# Motor_2.net
KiCad netlist of a schematic drawn in Altium Designer
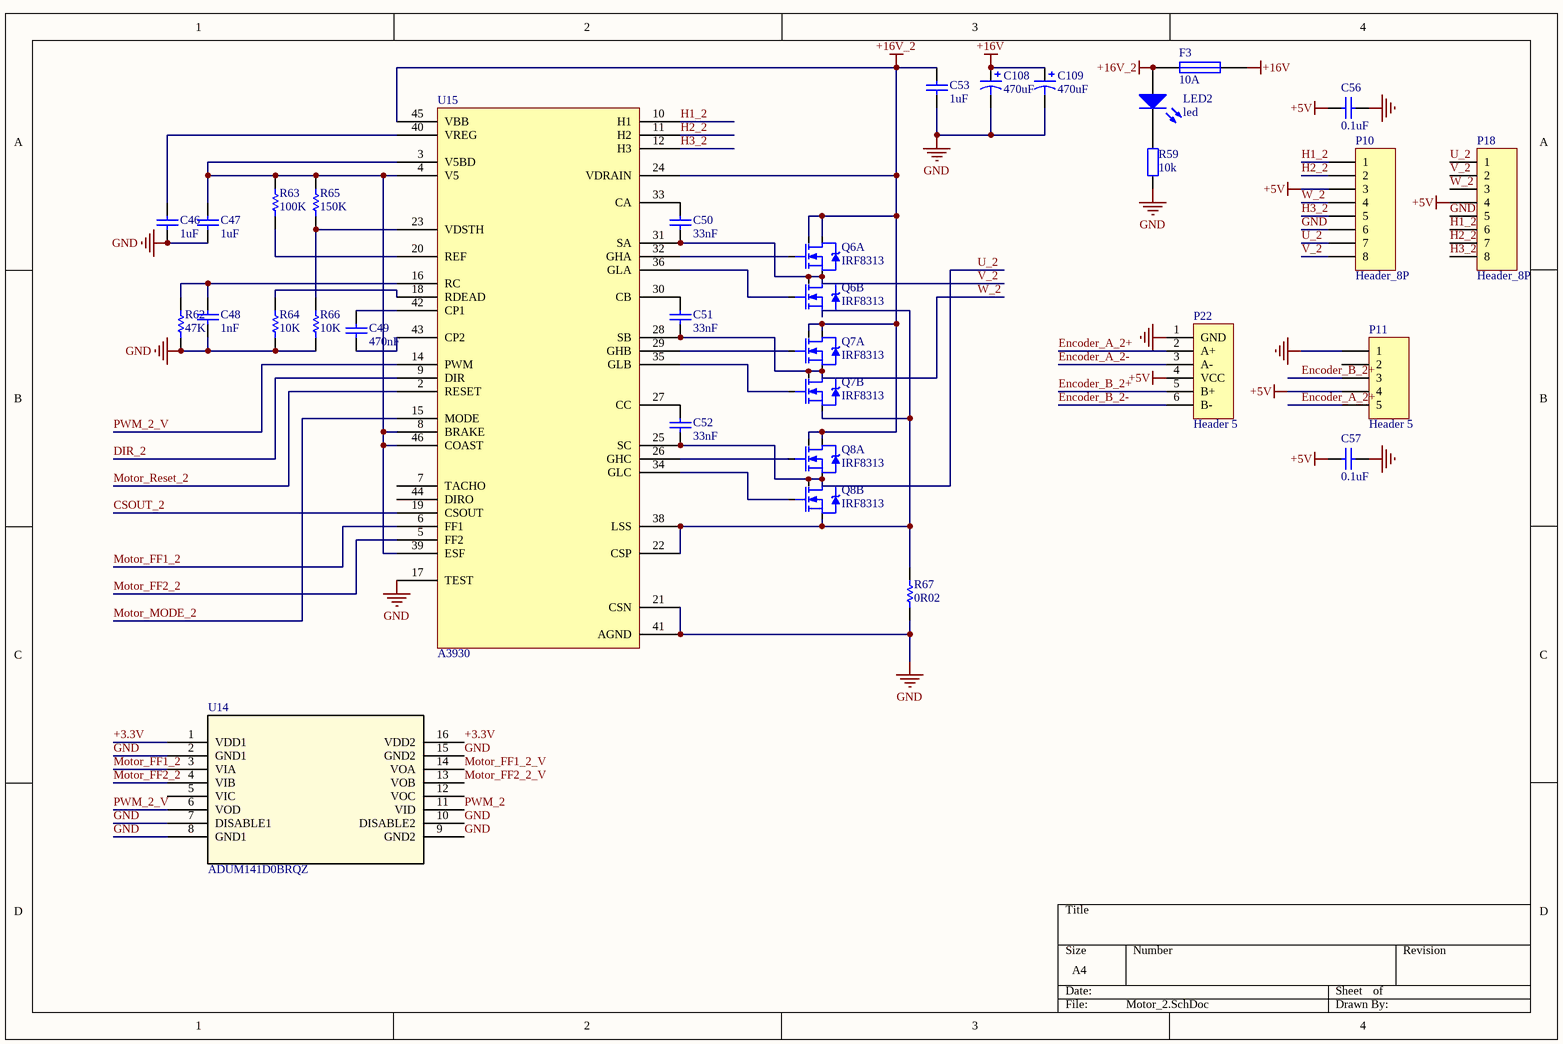
[diagram p0: Motor_2.SchDoc]

(export (version "E")
  (design (tool "Eeschema 10.0.6"))
  (components
    (comp (ref "C46")
      (value "1uF")
      (footprint "0603C")
      (description "Capacitor")
      (fields
        (field (name "MANUFACTURER") "Generic Components")
        (field (name "Comment") "1uf")
        (field (name "PUBLISHER") "Altium Hobart Technology Centre")
      )
      (libsource (lib "hp_2018_03") (part "Cap"))
    )
    (comp (ref "C47")
      (value "1uF")
      (footprint "0603C")
      (description "Capacitor")
      (fields
        (field (name "MANUFACTURER") "Generic Components")
        (field (name "Comment") "1uf")
        (field (name "PUBLISHER") "Altium Hobart Technology Centre")
      )
      (libsource (lib "hp_2018_03") (part "Cap"))
    )
    (comp (ref "C48")
      (value "1nF")
      (footprint "0603C")
      (description "Capacitor")
      (fields
        (field (name "MANUFACTURER") "Generic Components")
        (field (name "Comment") "1nf")
        (field (name "PUBLISHER") "Altium Hobart Technology Centre")
      )
      (libsource (lib "hp_2018_03") (part "Cap"))
    )
    (comp (ref "C49")
      (value "470nF")
      (footprint "0603C")
      (description "Capacitor")
      (fields
        (field (name "MANUFACTURER") "Generic Components")
        (field (name "Comment") "470nf")
        (field (name "PUBLISHER") "Altium Hobart Technology Centre")
      )
      (libsource (lib "hp_2018_03") (part "Cap"))
    )
    (comp (ref "C50")
      (value "33nF")
      (footprint "0603C")
      (description "Capacitor")
      (fields
        (field (name "MANUFACTURER") "Generic Components")
        (field (name "Comment") "33nf")
        (field (name "PUBLISHER") "Altium Hobart Technology Centre")
      )
      (libsource (lib "hp_2018_03") (part "Cap"))
    )
    (comp (ref "C51")
      (value "33nF")
      (footprint "0603C")
      (description "Capacitor")
      (fields
        (field (name "MANUFACTURER") "Generic Components")
        (field (name "Comment") "33nf")
        (field (name "PUBLISHER") "Altium Hobart Technology Centre")
      )
      (libsource (lib "hp_2018_03") (part "Cap"))
    )
    (comp (ref "C52")
      (value "33nF")
      (footprint "0603C")
      (description "Capacitor")
      (fields
        (field (name "MANUFACTURER") "Generic Components")
        (field (name "Comment") "33nf")
        (field (name "PUBLISHER") "Altium Hobart Technology Centre")
      )
      (libsource (lib "hp_2018_03") (part "Cap"))
    )
    (comp (ref "C53")
      (value "1uF")
      (footprint "0603C")
      (description "Capacitor")
      (fields
        (field (name "MANUFACTURER") "Generic Components")
        (field (name "Comment") "1uf")
        (field (name "PUBLISHER") "Altium Hobart Technology Centre")
      )
      (libsource (lib "hp_2018_03") (part "Cap"))
    )
    (comp (ref "C56")
      (value "0.1uF")
      (footprint "0603C")
      (description "Capacitor")
      (fields
        (field (name "MANUFACTURER") "Generic Components")
        (field (name "Comment") "0.1uf")
        (field (name "PUBLISHER") "Altium Hobart Technology Centre")
      )
      (libsource (lib "hp_2018_03") (part "Cap"))
    )
    (comp (ref "C57")
      (value "0.1uF")
      (footprint "0603C")
      (description "Capacitor")
      (fields
        (field (name "MANUFACTURER") "Generic Components")
        (field (name "Comment") "0.1uf")
        (field (name "PUBLISHER") "Altium Hobart Technology Centre")
      )
      (libsource (lib "hp_2018_03") (part "Cap"))
    )
    (comp (ref "C108")
      (value "470uF")
      (footprint "470uF")
      (description "Polarized Capacitor (Radial)")
      (fields (field (name "PUBLISHER") "Altium Limited"))
      (libsource (lib "Miscellaneous Devices") (part "Cap Pol1"))
    )
    (comp (ref "C109")
      (value "470uF")
      (footprint "470uF")
      (description "Polarized Capacitor (Radial)")
      (fields (field (name "PUBLISHER") "Altium Limited"))
      (libsource (lib "Miscellaneous Devices") (part "Cap Pol1"))
    )
    (comp (ref "F3")
      (value "10A")
      (footprint "Main_Board:FUSE_HEADER")
      (libsource (lib "Integrated_Library2") (part "FUSE"))
    )
    (comp (ref "LED2")
      (value "led")
      (footprint "0603_diode")
      (libsource (lib "Integrated_Library2") (part "led"))
    )
    (comp (ref "P10")
      (value "Header_8P")
      (footprint "8P - WF25122")
      (description "Used for Motor connection in ZJUNlict")
      (libsource (lib "Integrated_Library2") (part "Header_8P"))
    )
    (comp (ref "P11")
      (value "Header 5")
      (footprint "SHDR5")
      (description "Header, 5-Pin")
      (fields (field (name "PUBLISHER") "Altium Limited"))
      (libsource (lib "Miscellaneous Connectors") (part "Header 5"))
    )
    (comp (ref "P18")
      (value "Header_8P")
      (footprint "SHDR8")
      (description "Used for Motor connection in ZJUNlict")
      (libsource (lib "Integrated_Library2") (part "Header_8P"))
    )
    (comp (ref "P22")
      (value "Header 5")
      (footprint "SHDR6")
      (description "Header, 5-Pin")
      (fields (field (name "PUBLISHER") "Altium Limited"))
      (libsource (lib "Main_Board") (part "Header 6"))
    )
    (comp (ref "Q6") (value "IRF8313") (footprint "so-8 bg") (libsource (lib "BLDC") (part "SO-8 IRF8313")))
    (comp (ref "Q7") (value "IRF8313") (footprint "so-8 bg") (libsource (lib "BLDC") (part "SO-8 IRF8313")))
    (comp (ref "Q8") (value "IRF8313") (footprint "so-8 bg") (libsource (lib "BLDC") (part "SO-8 IRF8313")))
    (comp (ref "R59") (value "10k") (footprint "0603") (libsource (lib "Integrated_Library2") (part "res")))
    (comp (ref "R62")
      (value "47K")
      (footprint "0603R")
      (description "Resistor")
      (fields
        (field (name "MANUFACTURER") "Generic Components")
        (field (name "Comment") "47k")
        (field (name "PUBLISHER") "Altium Hobart Technology Centre")
      )
      (libsource (lib "hp_2018_03") (part "Res1"))
    )
    (comp (ref "R63")
      (value "100K")
      (footprint "0603R")
      (description "Resistor")
      (fields
        (field (name "MANUFACTURER") "Generic Components")
        (field (name "Comment") "100k")
        (field (name "PUBLISHER") "Altium Hobart Technology Centre")
      )
      (libsource (lib "hp_2018_03") (part "Res1"))
    )
    (comp (ref "R64")
      (value "10K")
      (footprint "0603R")
      (description "Resistor")
      (fields
        (field (name "MANUFACTURER") "Generic Components")
        (field (name "Comment") "10k")
        (field (name "PUBLISHER") "Altium Hobart Technology Centre")
      )
      (libsource (lib "hp_2018_03") (part "Res1"))
    )
    (comp (ref "R65")
      (value "150K")
      (footprint "0603R")
      (description "Resistor")
      (fields
        (field (name "MANUFACTURER") "Generic Components")
        (field (name "Comment") "100k")
        (field (name "PUBLISHER") "Altium Hobart Technology Centre")
      )
      (libsource (lib "hp_2018_03") (part "Res1"))
    )
    (comp (ref "R66")
      (value "10K")
      (footprint "0603R")
      (description "Resistor")
      (fields
        (field (name "MANUFACTURER") "Generic Components")
        (field (name "Comment") "10k")
        (field (name "PUBLISHER") "Altium Hobart Technology Centre")
      )
      (libsource (lib "hp_2018_03") (part "Res1"))
    )
    (comp (ref "R67")
      (value "0R02")
      (footprint "1206 10A")
      (description "Resistor")
      (fields
        (field (name "MANUFACTURER") "Generic Components")
        (field (name "Comment") "0.02")
        (field (name "PUBLISHER") "Altium Hobart Technology Centre")
      )
      (libsource (lib "hp_2018_03") (part "Res1"))
    )
    (comp (ref "U14")
      (value "ADUM141D0BRQZ")
      (footprint "Main_Board:RQ_16")
      (description "Imported")
      (libsource (lib "Main_Board") (part "ADUM141D0BRQZ"))
    )
    (comp (ref "U15") (value "A3930") (footprint "LQFP-48") (libsource (lib "BLDC") (part "LQFP 48")))
  )
  (nets
    (net (code "1") (name "+5V") (class "Default")
      (node (ref "C56") (pin "2") (pinfunction "2_2") (pintype "passive"))
      (node (ref "C57") (pin "2") (pinfunction "2_2") (pintype "passive"))
      (node (ref "P10") (pin "3") (pinfunction "3_3") (pintype "passive"))
      (node (ref "P11") (pin "4") (pinfunction "4_4") (pintype "passive"))
      (node (ref "P18") (pin "4") (pinfunction "4_4") (pintype "passive"))
      (node (ref "P22") (pin "4") (pinfunction "VCC_4") (pintype "passive"))
    )
    (net (code "2") (name "+16V") (class "Default")
      (node (ref "C108") (pin "1") (pinfunction "1_1") (pintype "passive"))
      (node (ref "C109") (pin "1") (pinfunction "1_1") (pintype "passive"))
      (node (ref "F3") (pin "1") (pinfunction "1_1") (pintype "passive"))
    )
    (net (code "3") (name "+16V_2") (class "Default")
      (node (ref "C53") (pin "2") (pinfunction "2_2") (pintype "passive"))
      (node (ref "F3") (pin "2") (pinfunction "2_2") (pintype "passive"))
      (node (ref "LED2") (pin "1") (pinfunction "A_1") (pintype "passive"))
      (node (ref "Q6") (pin "7") (pinfunction "D2_7") (pintype "passive"))
      (node (ref "Q6") (pin "8") (pinfunction "D2_8") (pintype "passive"))
      (node (ref "Q7") (pin "7") (pinfunction "D2_7") (pintype "passive"))
      (node (ref "Q7") (pin "8") (pinfunction "D2_8") (pintype "passive"))
      (node (ref "Q8") (pin "7") (pinfunction "D2_7") (pintype "passive"))
      (node (ref "Q8") (pin "8") (pinfunction "D2_8") (pintype "passive"))
      (node (ref "U15") (pin "24") (pinfunction "VDRAIN_24") (pintype "passive"))
      (node (ref "U15") (pin "45") (pinfunction "VBB_45") (pintype "passive"))
    )
    (net (code "4") (name "/+3.3V") (class "Default")
      (node (ref "U14") (pin "1") (pinfunction "VDD1_1") (pintype "passive"))
      (node (ref "U14") (pin "16") (pinfunction "VDD2_16") (pintype "passive"))
    )
    (net (code "5") (name "/CSOUT_2") (class "Default")
      (node (ref "U15") (pin "19") (pinfunction "CSOUT_19") (pintype "passive"))
    )
    (net (code "6") (name "/DIR_2") (class "Default")
      (node (ref "U15") (pin "9") (pinfunction "DIR_9") (pintype "passive"))
    )
    (net (code "7") (name "/Encoder_A_2+") (class "Default")
      (node (ref "P11") (pin "5") (pinfunction "5_5") (pintype "passive"))
      (node (ref "P22") (pin "2") (pinfunction "A+_2") (pintype "passive"))
    )
    (net (code "8") (name "/Encoder_A_2-") (class "Default")
      (node (ref "P22") (pin "3") (pinfunction "A-_3") (pintype "passive"))
    )
    (net (code "9") (name "/Encoder_B_2+") (class "Default")
      (node (ref "P11") (pin "3") (pinfunction "3_3") (pintype "passive"))
      (node (ref "P22") (pin "5") (pinfunction "B+_5") (pintype "passive"))
    )
    (net (code "10") (name "/Encoder_B_2-") (class "Default")
      (node (ref "P22") (pin "6") (pinfunction "B-_6") (pintype "passive"))
    )
    (net (code "11") (name "/H1_2") (class "Default")
      (node (ref "P10") (pin "1") (pinfunction "1_1") (pintype "passive"))
      (node (ref "P18") (pin "6") (pinfunction "6_6") (pintype "passive"))
      (node (ref "U15") (pin "10") (pinfunction "H1_10") (pintype "passive"))
    )
    (net (code "12") (name "/H2_2") (class "Default")
      (node (ref "P10") (pin "2") (pinfunction "2_2") (pintype "passive"))
      (node (ref "P18") (pin "7") (pinfunction "7_7") (pintype "passive"))
      (node (ref "U15") (pin "11") (pinfunction "H2_11") (pintype "passive"))
    )
    (net (code "13") (name "/H3_2") (class "Default")
      (node (ref "P10") (pin "5") (pinfunction "5_5") (pintype "passive"))
      (node (ref "P18") (pin "8") (pinfunction "8_8") (pintype "passive"))
      (node (ref "U15") (pin "12") (pinfunction "H3_12") (pintype "passive"))
    )
    (net (code "14") (name "/Motor_FF1_2") (class "Default")
      (node (ref "U14") (pin "3") (pinfunction "VIA_3") (pintype "passive"))
      (node (ref "U15") (pin "6") (pinfunction "FF1_6") (pintype "passive"))
    )
    (net (code "15") (name "/Motor_FF1_2_V") (class "Default")
      (node (ref "U14") (pin "14") (pinfunction "VOA_14") (pintype "passive"))
    )
    (net (code "16") (name "/Motor_FF2_2") (class "Default")
      (node (ref "U14") (pin "4") (pinfunction "VIB_4") (pintype "passive"))
      (node (ref "U15") (pin "5") (pinfunction "FF2_5") (pintype "passive"))
    )
    (net (code "17") (name "/Motor_FF2_2_V") (class "Default")
      (node (ref "U14") (pin "13") (pinfunction "VOB_13") (pintype "passive"))
    )
    (net (code "18") (name "/Motor_MODE_2") (class "Default")
      (node (ref "U15") (pin "15") (pinfunction "MODE_15") (pintype "passive"))
    )
    (net (code "19") (name "/Motor_Reset_2") (class "Default")
      (node (ref "U15") (pin "2") (pinfunction "RESET_2") (pintype "passive"))
    )
    (net (code "20") (name "/PWM_2") (class "Default")
      (node (ref "U14") (pin "11") (pinfunction "VID_11") (pintype "passive"))
    )
    (net (code "21") (name "/PWM_2_V") (class "Default")
      (node (ref "U14") (pin "6") (pinfunction "VOD_6") (pintype "passive"))
      (node (ref "U15") (pin "14") (pinfunction "PWM_14") (pintype "passive"))
    )
    (net (code "22") (name "/U_2") (class "Default")
      (node (ref "C52") (pin "1") (pinfunction "1_1") (pintype "passive"))
      (node (ref "P10") (pin "7") (pinfunction "7_7") (pintype "passive"))
      (node (ref "P18") (pin "1") (pinfunction "1_1") (pintype "passive"))
      (node (ref "Q8") (pin "1") (pinfunction "S2_1") (pintype "passive"))
      (node (ref "Q8") (pin "5") (pinfunction "D1_5") (pintype "passive"))
      (node (ref "Q8") (pin "6") (pinfunction "D1_6") (pintype "passive"))
      (node (ref "U15") (pin "25") (pinfunction "SC_25") (pintype "passive"))
    )
    (net (code "23") (name "/V_2") (class "Default")
      (node (ref "C50") (pin "1") (pinfunction "1_1") (pintype "passive"))
      (node (ref "P10") (pin "8") (pinfunction "8_8") (pintype "passive"))
      (node (ref "P18") (pin "2") (pinfunction "2_2") (pintype "passive"))
      (node (ref "Q6") (pin "1") (pinfunction "S2_1") (pintype "passive"))
      (node (ref "Q6") (pin "5") (pinfunction "D1_5") (pintype "passive"))
      (node (ref "Q6") (pin "6") (pinfunction "D1_6") (pintype "passive"))
      (node (ref "U15") (pin "31") (pinfunction "SA_31") (pintype "passive"))
    )
    (net (code "24") (name "/W_2") (class "Default")
      (node (ref "C51") (pin "1") (pinfunction "1_1") (pintype "passive"))
      (node (ref "P10") (pin "4") (pinfunction "4_4") (pintype "passive"))
      (node (ref "P18") (pin "3") (pinfunction "3_3") (pintype "passive"))
      (node (ref "Q7") (pin "1") (pinfunction "S2_1") (pintype "passive"))
      (node (ref "Q7") (pin "5") (pinfunction "D1_5") (pintype "passive"))
      (node (ref "Q7") (pin "6") (pinfunction "D1_6") (pintype "passive"))
      (node (ref "U15") (pin "28") (pinfunction "SB_28") (pintype "passive"))
    )
    (net (code "25") (name "GND") (class "Default")
      (node (ref "C108") (pin "2") (pinfunction "2_2") (pintype "passive"))
      (node (ref "C109") (pin "2") (pinfunction "2_2") (pintype "passive"))
      (node (ref "C46") (pin "1") (pinfunction "1_1") (pintype "passive"))
      (node (ref "C47") (pin "1") (pinfunction "1_1") (pintype "passive"))
      (node (ref "C48") (pin "1") (pinfunction "1_1") (pintype "passive"))
      (node (ref "C53") (pin "1") (pinfunction "1_1") (pintype "passive"))
      (node (ref "C56") (pin "1") (pinfunction "1_1") (pintype "passive"))
      (node (ref "C57") (pin "1") (pinfunction "1_1") (pintype "passive"))
      (node (ref "P10") (pin "6") (pinfunction "6_6") (pintype "passive"))
      (node (ref "P11") (pin "1") (pinfunction "1_1") (pintype "passive"))
      (node (ref "P18") (pin "5") (pinfunction "5_5") (pintype "passive"))
      (node (ref "P22") (pin "1") (pinfunction "GND_1") (pintype "passive"))
      (node (ref "R59") (pin "1") (pinfunction "1_1") (pintype "passive"))
      (node (ref "R62") (pin "1") (pinfunction "1_1") (pintype "passive"))
      (node (ref "R64") (pin "1") (pinfunction "1_1") (pintype "passive"))
      (node (ref "R66") (pin "1") (pinfunction "1_1") (pintype "passive"))
      (node (ref "R67") (pin "1") (pinfunction "1_1") (pintype "passive"))
      (node (ref "U14") (pin "10") (pinfunction "DISABLE2_10") (pintype "passive"))
      (node (ref "U14") (pin "15") (pinfunction "GND2_15") (pintype "passive"))
      (node (ref "U14") (pin "2") (pinfunction "GND1_2") (pintype "passive"))
      (node (ref "U14") (pin "7") (pinfunction "DISABLE1_7") (pintype "passive"))
      (node (ref "U14") (pin "8") (pinfunction "GND1_8") (pintype "passive"))
      (node (ref "U14") (pin "9") (pinfunction "GND2_9") (pintype "passive"))
      (node (ref "U15") (pin "17") (pinfunction "TEST_17") (pintype "passive"))
      (node (ref "U15") (pin "21") (pinfunction "CSN_21") (pintype "passive"))
      (node (ref "U15") (pin "41") (pinfunction "AGND_41") (pintype "passive"))
    )
    (net (code "26") (name "Net-(LED2-K)") (class "Default")
      (node (ref "LED2") (pin "2") (pinfunction "K_2") (pintype "passive"))
      (node (ref "R59") (pin "2") (pinfunction "2_2") (pintype "passive"))
    )
    (net (code "27") (name "Net-(Q6A-G2)") (class "Default")
      (node (ref "Q6") (pin "2") (pinfunction "G2_2") (pintype "passive"))
      (node (ref "U15") (pin "32") (pinfunction "GHA_32") (pintype "passive"))
    )
    (net (code "28") (name "Net-(Q6B-G1)") (class "Default")
      (node (ref "Q6") (pin "4") (pinfunction "G1_4") (pintype "passive"))
      (node (ref "U15") (pin "36") (pinfunction "GLA_36") (pintype "passive"))
    )
    (net (code "29") (name "Net-(Q6B-S1)") (class "Default")
      (node (ref "Q6") (pin "3") (pinfunction "S1_3") (pintype "passive"))
      (node (ref "Q7") (pin "3") (pinfunction "S1_3") (pintype "passive"))
      (node (ref "Q8") (pin "3") (pinfunction "S1_3") (pintype "passive"))
      (node (ref "R67") (pin "2") (pinfunction "2_2") (pintype "passive"))
      (node (ref "U15") (pin "22") (pinfunction "CSP_22") (pintype "passive"))
      (node (ref "U15") (pin "38") (pinfunction "LSS_38") (pintype "passive"))
    )
    (net (code "30") (name "Net-(Q7A-G2)") (class "Default")
      (node (ref "Q7") (pin "2") (pinfunction "G2_2") (pintype "passive"))
      (node (ref "U15") (pin "29") (pinfunction "GHB_29") (pintype "passive"))
    )
    (net (code "31") (name "Net-(Q7B-G1)") (class "Default")
      (node (ref "Q7") (pin "4") (pinfunction "G1_4") (pintype "passive"))
      (node (ref "U15") (pin "35") (pinfunction "GLB_35") (pintype "passive"))
    )
    (net (code "32") (name "Net-(Q8A-G2)") (class "Default")
      (node (ref "Q8") (pin "2") (pinfunction "G2_2") (pintype "passive"))
      (node (ref "U15") (pin "26") (pinfunction "GHC_26") (pintype "passive"))
    )
    (net (code "33") (name "Net-(Q8B-G1)") (class "Default")
      (node (ref "Q8") (pin "4") (pinfunction "G1_4") (pintype "passive"))
      (node (ref "U15") (pin "34") (pinfunction "GLC_34") (pintype "passive"))
    )
    (net (code "34") (name "Net-(U15-BRAKE)") (class "Default")
      (node (ref "C47") (pin "2") (pinfunction "2_2") (pintype "passive"))
      (node (ref "R63") (pin "2") (pinfunction "2_2") (pintype "passive"))
      (node (ref "R65") (pin "2") (pinfunction "2_2") (pintype "passive"))
      (node (ref "U15") (pin "3") (pinfunction "V5BD_3") (pintype "passive"))
      (node (ref "U15") (pin "39") (pinfunction "ESF_39") (pintype "passive"))
      (node (ref "U15") (pin "4") (pinfunction "V5_4") (pintype "passive"))
      (node (ref "U15") (pin "46") (pinfunction "COAST_46") (pintype "passive"))
      (node (ref "U15") (pin "8") (pinfunction "BRAKE_8") (pintype "passive"))
    )
    (net (code "35") (name "Net-(U15-CA)") (class "Default")
      (node (ref "C50") (pin "2") (pinfunction "2_2") (pintype "passive"))
      (node (ref "U15") (pin "33") (pinfunction "CA_33") (pintype "passive"))
    )
    (net (code "36") (name "Net-(U15-CB)") (class "Default")
      (node (ref "C51") (pin "2") (pinfunction "2_2") (pintype "passive"))
      (node (ref "U15") (pin "30") (pinfunction "CB_30") (pintype "passive"))
    )
    (net (code "37") (name "Net-(U15-CC)") (class "Default")
      (node (ref "C52") (pin "2") (pinfunction "2_2") (pintype "passive"))
      (node (ref "U15") (pin "27") (pinfunction "CC_27") (pintype "passive"))
    )
    (net (code "38") (name "Net-(U15-CP1)") (class "Default")
      (node (ref "C49") (pin "2") (pinfunction "2_2") (pintype "passive"))
      (node (ref "U15") (pin "42") (pinfunction "CP1_42") (pintype "passive"))
    )
    (net (code "39") (name "Net-(U15-CP2)") (class "Default")
      (node (ref "C49") (pin "1") (pinfunction "1_1") (pintype "passive"))
      (node (ref "U15") (pin "43") (pinfunction "CP2_43") (pintype "passive"))
    )
    (net (code "40") (name "Net-(U15-RC)") (class "Default")
      (node (ref "C48") (pin "2") (pinfunction "2_2") (pintype "passive"))
      (node (ref "R62") (pin "2") (pinfunction "2_2") (pintype "passive"))
      (node (ref "U15") (pin "16") (pinfunction "RC_16") (pintype "passive"))
    )
    (net (code "41") (name "Net-(U15-RDEAD)") (class "Default")
      (node (ref "R64") (pin "2") (pinfunction "2_2") (pintype "passive"))
      (node (ref "U15") (pin "18") (pinfunction "RDEAD_18") (pintype "passive"))
    )
    (net (code "42") (name "Net-(U15-REF)") (class "Default")
      (node (ref "R63") (pin "1") (pinfunction "1_1") (pintype "passive"))
      (node (ref "U15") (pin "20") (pinfunction "REF_20") (pintype "passive"))
    )
    (net (code "43") (name "Net-(U15-VDSTH)") (class "Default")
      (node (ref "R65") (pin "1") (pinfunction "1_1") (pintype "passive"))
      (node (ref "R66") (pin "2") (pinfunction "2_2") (pintype "passive"))
      (node (ref "U15") (pin "23") (pinfunction "VDSTH_23") (pintype "passive"))
    )
    (net (code "44") (name "Net-(U15-VREG)") (class "Default")
      (node (ref "C46") (pin "2") (pinfunction "2_2") (pintype "passive"))
      (node (ref "U15") (pin "40") (pinfunction "VREG_40") (pintype "passive"))
    )
    (net (code "45") (name "unconnected-(P11-Pad2)") (class "Default")
      (node (ref "P11") (pin "2") (pinfunction "2_2") (pintype "passive"))
    )
    (net (code "46") (name "unconnected-(U14-VIC-Pad5)") (class "Default")
      (node (ref "U14") (pin "5") (pinfunction "VIC_5") (pintype "passive"))
    )
    (net (code "47") (name "unconnected-(U14-VOC-Pad12)") (class "Default")
      (node (ref "U14") (pin "12") (pinfunction "VOC_12") (pintype "passive"))
    )
    (net (code "48") (name "unconnected-(U15-DIRO-Pad44)") (class "Default")
      (node (ref "U15") (pin "44") (pinfunction "DIRO_44") (pintype "passive"))
    )
    (net (code "49") (name "unconnected-(U15-TACHO-Pad7)") (class "Default")
      (node (ref "U15") (pin "7") (pinfunction "TACHO_7") (pintype "passive"))
    )
  )
)
